# camera.net
KiCad netlist of a schematic drawn in Altium Designer
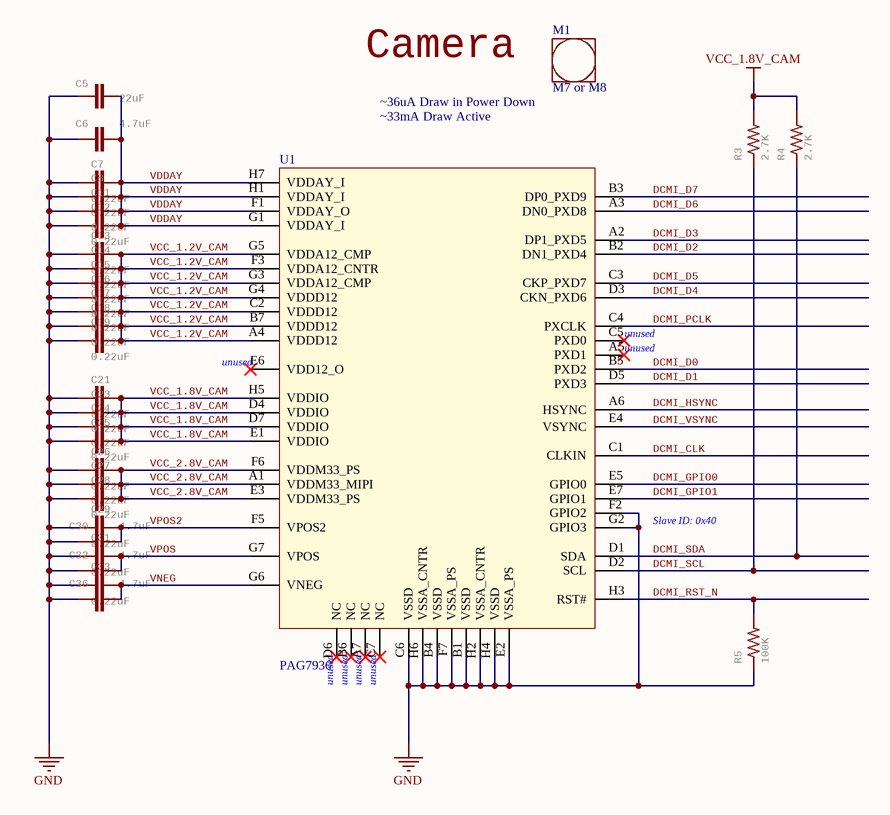
[diagram p0: camera.SchDoc]

(export (version "E")
  (design (tool "Eeschema 10.0.6"))
  (components
    (comp (ref "C5")
      (value "22uF")
      (footprint "0805")
      (fields (field (name "MPN") "CL21A226MQQNNNE"))
      (libsource (lib "openmv-ae3") (part "22UF-0805-6.3V-20%"))
    )
    (comp (ref "C6")
      (value "4.7uF")
      (footprint "0402-CAP")
      (description "0402 (1005 Metric) Nick Garner - TeleSense")
      (fields (field (name "MPN") "JMK105BBJ475MV-F"))
      (libsource (lib "openmv-ae3") (part "CAP_0402"))
    )
    (comp (ref "C7")
      (value "0.22uF")
      (footprint "C0201")
      (description "CAPACITOR, European symbol")
      (fields (field (name "MPN") "GRM033R60J224ME15D"))
      (libsource (lib "openmv-ae3") (part "C-EUC0201"))
    )
    (comp (ref "C8")
      (value "0.22uF")
      (footprint "C0201")
      (description "CAPACITOR, European symbol")
      (fields (field (name "MPN") "GRM033R60J224ME15D"))
      (libsource (lib "openmv-ae3") (part "C-EUC0201"))
    )
    (comp (ref "C11")
      (value "0.22uF")
      (footprint "C0201")
      (description "CAPACITOR, European symbol")
      (fields (field (name "MPN") "GRM033R60J224ME15D"))
      (libsource (lib "openmv-ae3") (part "C-EUC0201"))
    )
    (comp (ref "C12")
      (value "0.22uF")
      (footprint "C0201")
      (description "CAPACITOR, European symbol")
      (fields (field (name "MPN") "GRM033R60J224ME15D"))
      (libsource (lib "openmv-ae3") (part "C-EUC0201"))
    )
    (comp (ref "C13")
      (value "0.22uF")
      (footprint "C0201")
      (description "CAPACITOR, European symbol")
      (fields (field (name "MPN") "GRM033R60J224ME15D"))
      (libsource (lib "openmv-ae3") (part "C-EUC0201"))
    )
    (comp (ref "C14")
      (value "0.22uF")
      (footprint "C0201")
      (description "CAPACITOR, European symbol")
      (fields (field (name "MPN") "GRM033R60J224ME15D"))
      (libsource (lib "openmv-ae3") (part "C-EUC0201"))
    )
    (comp (ref "C15")
      (value "0.22uF")
      (footprint "C0201")
      (description "CAPACITOR, European symbol")
      (fields (field (name "MPN") "GRM033R60J224ME15D"))
      (libsource (lib "openmv-ae3") (part "C-EUC0201"))
    )
    (comp (ref "C16")
      (value "0.22uF")
      (footprint "C0201")
      (description "CAPACITOR, European symbol")
      (fields (field (name "MPN") "GRM033R60J224ME15D"))
      (libsource (lib "openmv-ae3") (part "C-EUC0201"))
    )
    (comp (ref "C17")
      (value "0.22uF")
      (footprint "C0201")
      (description "CAPACITOR, European symbol")
      (fields (field (name "MPN") "GRM033R60J224ME15D"))
      (libsource (lib "openmv-ae3") (part "C-EUC0201"))
    )
    (comp (ref "C18")
      (value "0.22uF")
      (footprint "C0201")
      (description "CAPACITOR, European symbol")
      (fields (field (name "MPN") "GRM033R60J224ME15D"))
      (libsource (lib "openmv-ae3") (part "C-EUC0201"))
    )
    (comp (ref "C19")
      (value "0.22uF")
      (footprint "C0201")
      (description "CAPACITOR, European symbol")
      (fields (field (name "MPN") "GRM033R60J224ME15D"))
      (libsource (lib "openmv-ae3") (part "C-EUC0201"))
    )
    (comp (ref "C21")
      (value "0.22uF")
      (footprint "C0201")
      (description "CAPACITOR, European symbol")
      (fields (field (name "MPN") "GRM033R60J224ME15D"))
      (libsource (lib "openmv-ae3") (part "C-EUC0201"))
    )
    (comp (ref "C23")
      (value "0.22uF")
      (footprint "C0201")
      (description "CAPACITOR, European symbol")
      (fields (field (name "MPN") "GRM033R60J224ME15D"))
      (libsource (lib "openmv-ae3") (part "C-EUC0201"))
    )
    (comp (ref "C24")
      (value "0.22uF")
      (footprint "C0201")
      (description "CAPACITOR, European symbol")
      (fields (field (name "MPN") "GRM033R60J224ME15D"))
      (libsource (lib "openmv-ae3") (part "C-EUC0201"))
    )
    (comp (ref "C25")
      (value "0.22uF")
      (footprint "C0201")
      (description "CAPACITOR, European symbol")
      (fields (field (name "MPN") "GRM033R60J224ME15D"))
      (libsource (lib "openmv-ae3") (part "C-EUC0201"))
    )
    (comp (ref "C26")
      (value "0.22uF")
      (footprint "C0201")
      (description "CAPACITOR, European symbol")
      (fields (field (name "MPN") "GRM033R60J224ME15D"))
      (libsource (lib "openmv-ae3") (part "C-EUC0201"))
    )
    (comp (ref "C27")
      (value "0.22uF")
      (footprint "C0201")
      (description "CAPACITOR, European symbol")
      (fields (field (name "MPN") "GRM033R60J224ME15D"))
      (libsource (lib "openmv-ae3") (part "C-EUC0201"))
    )
    (comp (ref "C28")
      (value "0.22uF")
      (footprint "C0201")
      (description "CAPACITOR, European symbol")
      (fields (field (name "MPN") "GRM033R60J224ME15D"))
      (libsource (lib "openmv-ae3") (part "C-EUC0201"))
    )
    (comp (ref "C29")
      (value "0.22uF")
      (footprint "C0201")
      (description "CAPACITOR, European symbol")
      (fields (field (name "MPN") "GRM033R60J224ME15D"))
      (libsource (lib "openmv-ae3") (part "C-EUC0201"))
    )
    (comp (ref "C30")
      (value "4.7uF")
      (footprint "0402-CAP")
      (description "0402 (1005 Metric) Nick Garner - TeleSense")
      (fields (field (name "MPN") "JMK105BBJ475MV-F"))
      (libsource (lib "openmv-ae3") (part "CAP_0402"))
    )
    (comp (ref "C31")
      (value "0.22uF")
      (footprint "C0201")
      (description "CAPACITOR, European symbol")
      (fields (field (name "MPN") "GRM033R60J224ME15D"))
      (libsource (lib "openmv-ae3") (part "C-EUC0201"))
    )
    (comp (ref "C32")
      (value "4.7uF")
      (footprint "0402-CAP")
      (description "0402 (1005 Metric) Nick Garner - TeleSense")
      (fields (field (name "MPN") "JMK105BBJ475MV-F"))
      (libsource (lib "openmv-ae3") (part "CAP_0402"))
    )
    (comp (ref "C33")
      (value "0.22uF")
      (footprint "C0201")
      (description "CAPACITOR, European symbol")
      (fields (field (name "MPN") "GRM033R60J224ME15D"))
      (libsource (lib "openmv-ae3") (part "C-EUC0201"))
    )
    (comp (ref "C36")
      (value "4.7uF")
      (footprint "0402-CAP")
      (description "0402 (1005 Metric) Nick Garner - TeleSense")
      (fields (field (name "MPN") "JMK105BBJ475MV-F"))
      (libsource (lib "openmv-ae3") (part "CAP_0402"))
    )
    (comp (ref "M1")
      (value "M7 or M8")
      (footprint "M7_M8")
      (libsource (lib "openmv-ae3") (part "M7_M8_LENS_MOUNT"))
    )
    (comp (ref "R3")
      (value "2.7K")
      (footprint "R0201")
      (fields (field (name "MPN") "RC0201JR-072K7L") (field (name "LIBRARYNAME") "sfe"))
      (libsource (lib "openmv-ae3") (part "RESISTOR0402-RES"))
    )
    (comp (ref "R4")
      (value "2.7K")
      (footprint "R0201")
      (fields (field (name "MPN") "RC0201JR-072K7L") (field (name "LIBRARYNAME") "sfe"))
      (libsource (lib "openmv-ae3") (part "RESISTOR0402-RES"))
    )
    (comp (ref "R5")
      (value "100K")
      (footprint "R0201")
      (fields (field (name "MPN") "RMCF0201FT100K") (field (name "LIBRARYNAME") "sfe"))
      (libsource (lib "openmv-ae3") (part "RESISTOR0402-RES"))
    )
    (comp (ref "U1")
      (value "PAG7936")
      (footprint "PAG7936")
      (fields (field (name "MF") "PixArt") (field (name "MPN") "PAG7936"))
      (libsource (lib "openmv-ae3") (part "PAG7936"))
    )
  )
  (nets
    (net (code "1") (name "/DCMI_CLK") (class "Default")
      (node (ref "U1") (pin "C1") (pinfunction "CLKIN_C1") (pintype "passive"))
    )
    (net (code "2") (name "/DCMI_D0") (class "Default")
      (node (ref "U1") (pin "B5") (pinfunction "PXD2_B5") (pintype "passive"))
    )
    (net (code "3") (name "/DCMI_D1") (class "Default")
      (node (ref "U1") (pin "D5") (pinfunction "PXD3_D5") (pintype "passive"))
    )
    (net (code "4") (name "/DCMI_D2") (class "Default")
      (node (ref "U1") (pin "B2") (pinfunction "DN1_PXD4_B2") (pintype "passive"))
    )
    (net (code "5") (name "/DCMI_D3") (class "Default")
      (node (ref "U1") (pin "A2") (pinfunction "DP1_PXD5_A2") (pintype "passive"))
    )
    (net (code "6") (name "/DCMI_D4") (class "Default")
      (node (ref "U1") (pin "D3") (pinfunction "CKN_PXD6_D3") (pintype "passive"))
    )
    (net (code "7") (name "/DCMI_D5") (class "Default")
      (node (ref "U1") (pin "C3") (pinfunction "CKP_PXD7_C3") (pintype "passive"))
    )
    (net (code "8") (name "/DCMI_D6") (class "Default")
      (node (ref "U1") (pin "A3") (pinfunction "DN0_PXD8_A3") (pintype "passive"))
    )
    (net (code "9") (name "/DCMI_D7") (class "Default")
      (node (ref "U1") (pin "B3") (pinfunction "DP0_PXD9_B3") (pintype "passive"))
    )
    (net (code "10") (name "/DCMI_GPIO0") (class "Default")
      (node (ref "U1") (pin "E5") (pinfunction "GPIO0_E5") (pintype "passive"))
    )
    (net (code "11") (name "/DCMI_GPIO1") (class "Default")
      (node (ref "U1") (pin "E7") (pinfunction "GPIO1_E7") (pintype "passive"))
    )
    (net (code "12") (name "/DCMI_HSYNC") (class "Default")
      (node (ref "U1") (pin "A6") (pinfunction "HSYNC_A6") (pintype "passive"))
    )
    (net (code "13") (name "/DCMI_PCLK") (class "Default")
      (node (ref "U1") (pin "C4") (pinfunction "PXCLK_C4") (pintype "passive"))
    )
    (net (code "14") (name "/DCMI_RST_N") (class "Default")
      (node (ref "R5") (pin "2") (pinfunction "2_2") (pintype "passive"))
      (node (ref "U1") (pin "H3") (pinfunction "RST#_H3") (pintype "passive"))
    )
    (net (code "15") (name "/DCMI_SCL") (class "Default")
      (node (ref "R3") (pin "1") (pinfunction "1_1") (pintype "passive"))
      (node (ref "U1") (pin "D2") (pinfunction "SCL_D2") (pintype "passive"))
    )
    (net (code "16") (name "/DCMI_SDA") (class "Default")
      (node (ref "R4") (pin "1") (pinfunction "1_1") (pintype "passive"))
      (node (ref "U1") (pin "D1") (pinfunction "SDA_D1") (pintype "passive"))
    )
    (net (code "17") (name "/DCMI_VSYNC") (class "Default")
      (node (ref "U1") (pin "E4") (pinfunction "VSYNC_E4") (pintype "passive"))
    )
    (net (code "18") (name "/VCC_1.2V_CAM") (class "Default")
      (node (ref "C13") (pin "2") (pinfunction "2_2") (pintype "passive"))
      (node (ref "C14") (pin "2") (pinfunction "2_2") (pintype "passive"))
      (node (ref "C15") (pin "2") (pinfunction "2_2") (pintype "passive"))
      (node (ref "C16") (pin "2") (pinfunction "2_2") (pintype "passive"))
      (node (ref "C17") (pin "2") (pinfunction "2_2") (pintype "passive"))
      (node (ref "C18") (pin "2") (pinfunction "2_2") (pintype "passive"))
      (node (ref "C19") (pin "2") (pinfunction "2_2") (pintype "passive"))
      (node (ref "U1") (pin "A4") (pinfunction "VDDD12_A4") (pintype "passive"))
      (node (ref "U1") (pin "B7") (pinfunction "VDDD12_B7") (pintype "passive"))
      (node (ref "U1") (pin "C2") (pinfunction "VDDD12_C2") (pintype "passive"))
      (node (ref "U1") (pin "F3") (pinfunction "VDDA12_CNTR_F3") (pintype "passive"))
      (node (ref "U1") (pin "G3") (pinfunction "VDDA12_CMP_G3") (pintype "passive"))
      (node (ref "U1") (pin "G4") (pinfunction "VDDD12_G4") (pintype "passive"))
      (node (ref "U1") (pin "G5") (pinfunction "VDDA12_CMP_G5") (pintype "passive"))
    )
    (net (code "19") (name "/VCC_2.8V_CAM") (class "Default")
      (node (ref "C26") (pin "2") (pinfunction "2_2") (pintype "passive"))
      (node (ref "C27") (pin "2") (pinfunction "2_2") (pintype "passive"))
      (node (ref "C28") (pin "2") (pinfunction "2_2") (pintype "passive"))
      (node (ref "U1") (pin "A1") (pinfunction "VDDM33_MIPI_A1") (pintype "passive"))
      (node (ref "U1") (pin "E3") (pinfunction "VDDM33_PS_E3") (pintype "passive"))
      (node (ref "U1") (pin "F6") (pinfunction "VDDM33_PS_F6") (pintype "passive"))
    )
    (net (code "20") (name "/VDDAY") (class "Default")
      (node (ref "C11") (pin "2") (pinfunction "2_2") (pintype "passive"))
      (node (ref "C12") (pin "2") (pinfunction "2_2") (pintype "passive"))
      (node (ref "C5") (pin "2") (pinfunction "2_2") (pintype "passive"))
      (node (ref "C6") (pin "2") (pinfunction "2_2") (pintype "passive"))
      (node (ref "C7") (pin "2") (pinfunction "2_2") (pintype "passive"))
      (node (ref "C8") (pin "2") (pinfunction "2_2") (pintype "passive"))
      (node (ref "U1") (pin "F1") (pinfunction "VDDAY_O_F1") (pintype "passive"))
      (node (ref "U1") (pin "G1") (pinfunction "VDDAY_I_G1") (pintype "passive"))
      (node (ref "U1") (pin "H1") (pinfunction "VDDAY_I_H1") (pintype "passive"))
      (node (ref "U1") (pin "H7") (pinfunction "VDDAY_I_H7") (pintype "passive"))
    )
    (net (code "21") (name "/VNEG") (class "Default")
      (node (ref "C33") (pin "2") (pinfunction "2_2") (pintype "passive"))
      (node (ref "C36") (pin "2") (pinfunction "2_2") (pintype "passive"))
      (node (ref "U1") (pin "G6") (pinfunction "VNEG_G6") (pintype "passive"))
    )
    (net (code "22") (name "/VPOS") (class "Default")
      (node (ref "C31") (pin "2") (pinfunction "2_2") (pintype "passive"))
      (node (ref "C32") (pin "2") (pinfunction "2_2") (pintype "passive"))
      (node (ref "U1") (pin "G7") (pinfunction "VPOS_G7") (pintype "passive"))
    )
    (net (code "23") (name "/VPOS2") (class "Default")
      (node (ref "C29") (pin "2") (pinfunction "2_2") (pintype "passive"))
      (node (ref "C30") (pin "2") (pinfunction "2_2") (pintype "passive"))
      (node (ref "U1") (pin "F5") (pinfunction "VPOS2_F5") (pintype "passive"))
    )
    (net (code "24") (name "GND") (class "Default")
      (node (ref "C11") (pin "1") (pinfunction "1_1") (pintype "passive"))
      (node (ref "C12") (pin "1") (pinfunction "1_1") (pintype "passive"))
      (node (ref "C13") (pin "1") (pinfunction "1_1") (pintype "passive"))
      (node (ref "C14") (pin "1") (pinfunction "1_1") (pintype "passive"))
      (node (ref "C15") (pin "1") (pinfunction "1_1") (pintype "passive"))
      (node (ref "C16") (pin "1") (pinfunction "1_1") (pintype "passive"))
      (node (ref "C17") (pin "1") (pinfunction "1_1") (pintype "passive"))
      (node (ref "C18") (pin "1") (pinfunction "1_1") (pintype "passive"))
      (node (ref "C19") (pin "1") (pinfunction "1_1") (pintype "passive"))
      (node (ref "C21") (pin "1") (pinfunction "1_1") (pintype "passive"))
      (node (ref "C23") (pin "1") (pinfunction "1_1") (pintype "passive"))
      (node (ref "C24") (pin "1") (pinfunction "1_1") (pintype "passive"))
      (node (ref "C25") (pin "1") (pinfunction "1_1") (pintype "passive"))
      (node (ref "C26") (pin "1") (pinfunction "1_1") (pintype "passive"))
      (node (ref "C27") (pin "1") (pinfunction "1_1") (pintype "passive"))
      (node (ref "C28") (pin "1") (pinfunction "1_1") (pintype "passive"))
      (node (ref "C29") (pin "1") (pinfunction "1_1") (pintype "passive"))
      (node (ref "C30") (pin "1") (pinfunction "1_1") (pintype "passive"))
      (node (ref "C31") (pin "1") (pinfunction "1_1") (pintype "passive"))
      (node (ref "C32") (pin "1") (pinfunction "1_1") (pintype "passive"))
      (node (ref "C33") (pin "1") (pinfunction "1_1") (pintype "passive"))
      (node (ref "C36") (pin "1") (pinfunction "1_1") (pintype "passive"))
      (node (ref "C5") (pin "1") (pinfunction "1_1") (pintype "passive"))
      (node (ref "C6") (pin "1") (pinfunction "1_1") (pintype "passive"))
      (node (ref "C7") (pin "1") (pinfunction "1_1") (pintype "passive"))
      (node (ref "C8") (pin "1") (pinfunction "1_1") (pintype "passive"))
      (node (ref "R5") (pin "1") (pinfunction "1_1") (pintype "passive"))
      (node (ref "U1") (pin "B1") (pinfunction "VSSD_B1") (pintype "passive"))
      (node (ref "U1") (pin "B4") (pinfunction "VSSD_B4") (pintype "passive"))
      (node (ref "U1") (pin "C6") (pinfunction "VSSD_C6") (pintype "passive"))
      (node (ref "U1") (pin "E2") (pinfunction "VSSA_PS_E2") (pintype "passive"))
      (node (ref "U1") (pin "F2") (pinfunction "GPIO2_F2") (pintype "passive"))
      (node (ref "U1") (pin "F7") (pinfunction "VSSA_PS_F7") (pintype "passive"))
      (node (ref "U1") (pin "G2") (pinfunction "GPIO3_G2") (pintype "passive"))
      (node (ref "U1") (pin "H2") (pinfunction "VSSA_CNTR_H2") (pintype "passive"))
      (node (ref "U1") (pin "H4") (pinfunction "VSSD_H4") (pintype "passive"))
      (node (ref "U1") (pin "H6") (pinfunction "VSSA_CNTR_H6") (pintype "passive"))
    )
    (net (code "25") (name "VCC_1.8V_CAM") (class "Default")
      (node (ref "C21") (pin "2") (pinfunction "2_2") (pintype "passive"))
      (node (ref "C23") (pin "2") (pinfunction "2_2") (pintype "passive"))
      (node (ref "C24") (pin "2") (pinfunction "2_2") (pintype "passive"))
      (node (ref "C25") (pin "2") (pinfunction "2_2") (pintype "passive"))
      (node (ref "R3") (pin "2") (pinfunction "2_2") (pintype "passive"))
      (node (ref "R4") (pin "2") (pinfunction "2_2") (pintype "passive"))
      (node (ref "U1") (pin "D4") (pinfunction "VDDIO_D4") (pintype "passive"))
      (node (ref "U1") (pin "D7") (pinfunction "VDDIO_D7") (pintype "passive"))
      (node (ref "U1") (pin "E1") (pinfunction "VDDIO_E1") (pintype "passive"))
      (node (ref "U1") (pin "H5") (pinfunction "VDDIO_H5") (pintype "passive"))
    )
    (net (code "26") (name "unconnected-(U1-NC-PadA7)") (class "Default")
      (node (ref "U1") (pin "A7") (pinfunction "NC_A7") (pintype "passive+no_connect"))
    )
    (net (code "27") (name "unconnected-(U1-NC-PadB6)") (class "Default")
      (node (ref "U1") (pin "B6") (pinfunction "NC_B6") (pintype "passive+no_connect"))
    )
    (net (code "28") (name "unconnected-(U1-NC-PadC7)") (class "Default")
      (node (ref "U1") (pin "C7") (pinfunction "NC_C7") (pintype "passive+no_connect"))
    )
    (net (code "29") (name "unconnected-(U1-NC-PadD6)") (class "Default")
      (node (ref "U1") (pin "D6") (pinfunction "NC_D6") (pintype "passive+no_connect"))
    )
    (net (code "30") (name "unconnected-(U1-PXD0-PadC5)") (class "Default")
      (node (ref "U1") (pin "C5") (pinfunction "PXD0_C5") (pintype "passive+no_connect"))
    )
    (net (code "31") (name "unconnected-(U1-PXD1-PadA5)") (class "Default")
      (node (ref "U1") (pin "A5") (pinfunction "PXD1_A5") (pintype "passive+no_connect"))
    )
    (net (code "32") (name "unconnected-(U1-VDD12_O-PadE6)") (class "Default")
      (node (ref "U1") (pin "E6") (pinfunction "VDD12_O_E6") (pintype "passive+no_connect"))
    )
  )
)
